# M117C.net
KiCad netlist of a schematic drawn in EAGLE
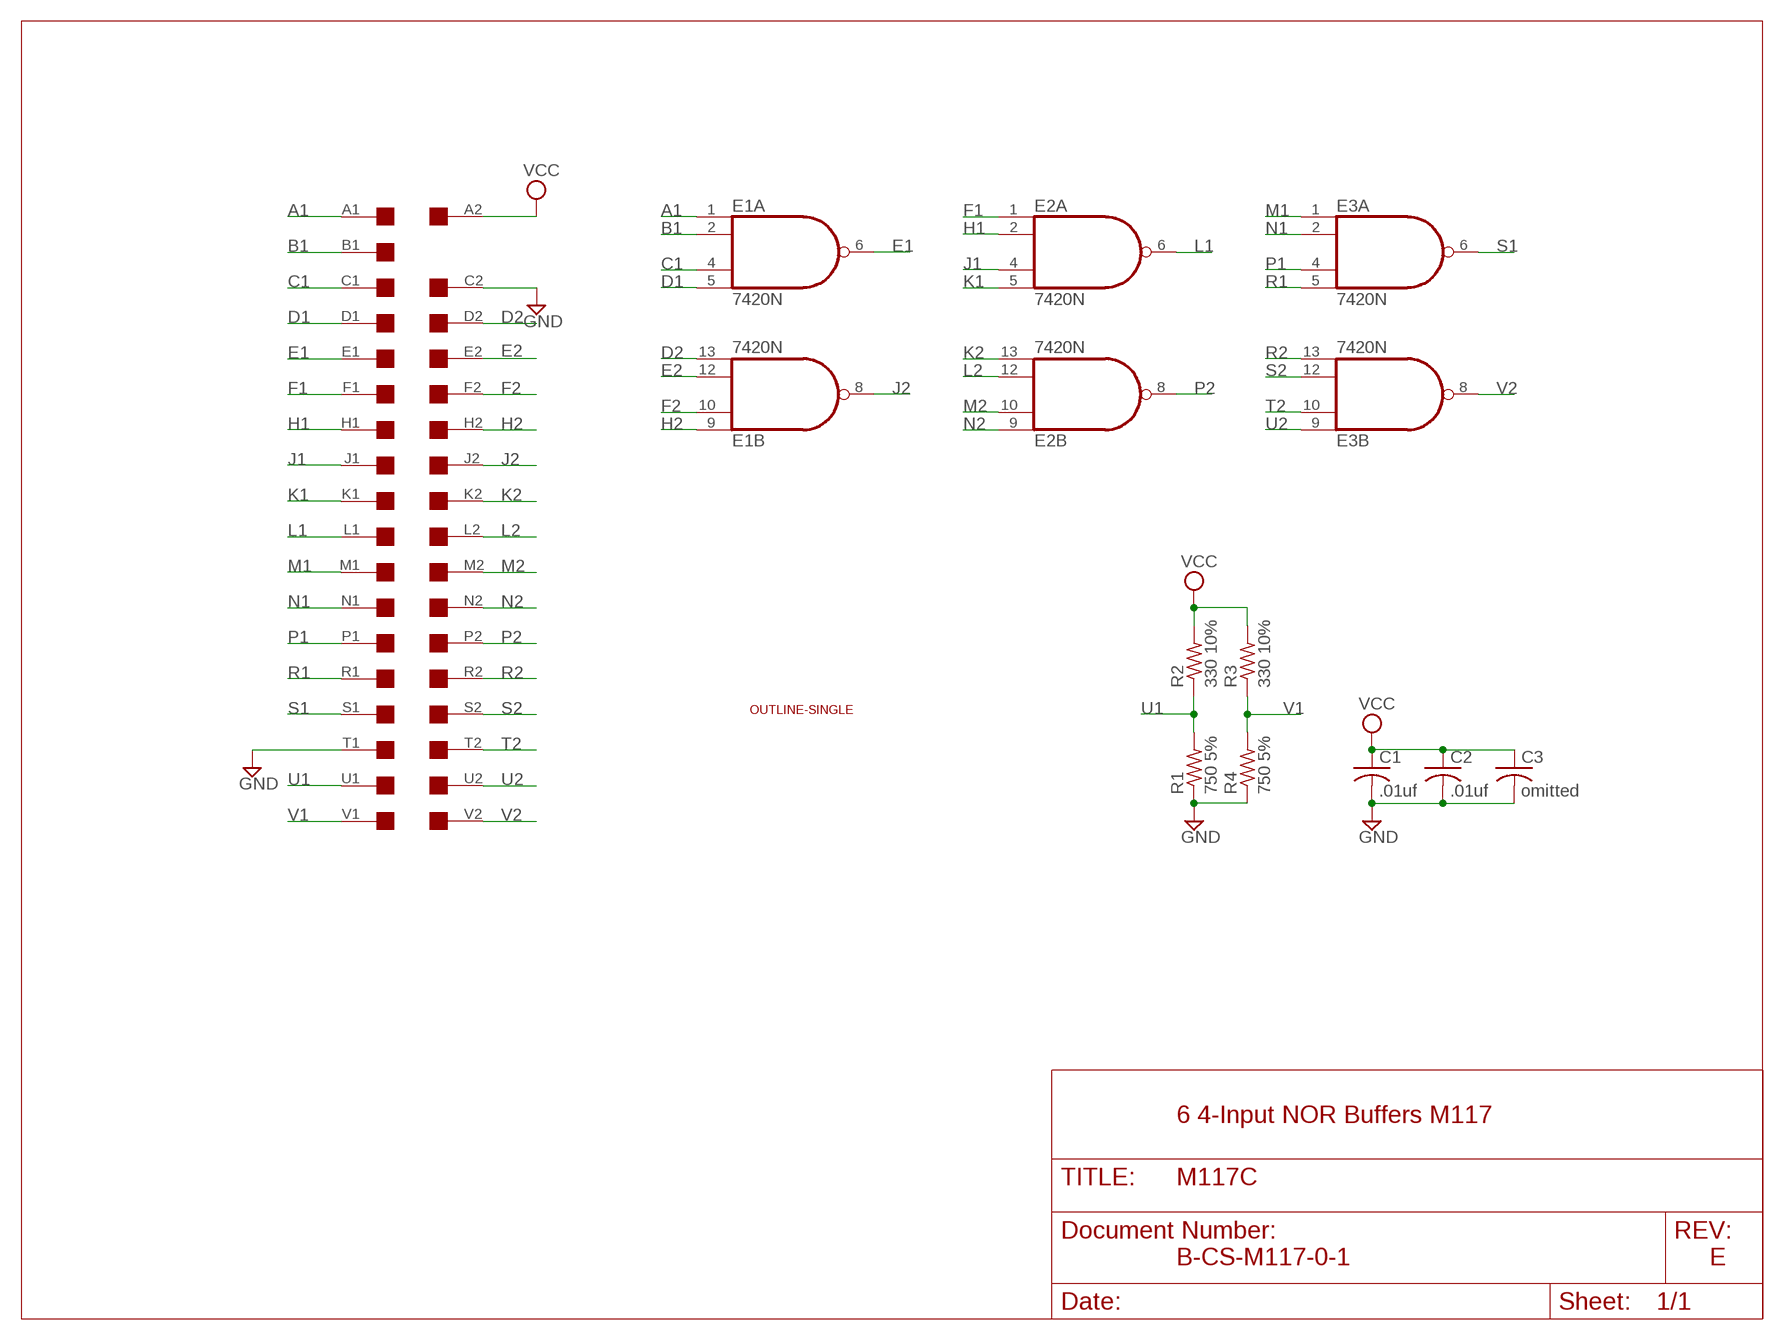
[diagram p0: schematic, sheet 1]

(export (version "E")
  (design (tool "Eeschema 10.0.6"))
  (components
    (comp (ref "C1")
      (value ".01uf")
      (footprint "eagle-import:C050-025X075")
      (libsource (lib "eagle-import") (part "C-US050-025X075"))
    )
    (comp (ref "C2")
      (value ".01uf")
      (footprint "eagle-import:C050-025X075")
      (libsource (lib "eagle-import") (part "C-US050-025X075"))
    )
    (comp (ref "C3")
      (value "omitted")
      (footprint "eagle-import:C050-025X075")
      (libsource (lib "eagle-import") (part "C-US050-025X075"))
    )
    (comp (ref "E1")
      (value "7420N")
      (footprint "eagle-import:DIL14")
      (libsource (lib "eagle-import") (part "7420NS"))
    )
    (comp (ref "E2")
      (value "7420N")
      (footprint "eagle-import:DIL14")
      (libsource (lib "eagle-import") (part "7420NS"))
    )
    (comp (ref "E3")
      (value "7420N")
      (footprint "eagle-import:DIL14")
      (libsource (lib "eagle-import") (part "7420NS"))
    )
    (comp (ref "R1")
      (value "750 5%")
      (footprint "eagle-import:0207_10")
      (libsource (lib "eagle-import") (part "R-US_0207/10"))
    )
    (comp (ref "R2")
      (value "330 10%")
      (footprint "eagle-import:0207_10")
      (libsource (lib "eagle-import") (part "R-US_0207/10"))
    )
    (comp (ref "R3")
      (value "330 10%")
      (footprint "eagle-import:0207_10")
      (libsource (lib "eagle-import") (part "R-US_0207/10"))
    )
    (comp (ref "R4")
      (value "750 5%")
      (footprint "eagle-import:0207_10")
      (libsource (lib "eagle-import") (part "R-US_0207/10"))
    )
    (comp (ref "U$1")
      (value "SINGLE")
      (footprint "eagle-import:EDGE-CON2")
      (libsource (lib "eagle-import") (part "SINGLE"))
    )
    (comp (ref "U$4")
      (value "OUTLINE-SINGLE")
      (footprint "eagle-import:SINGLE")
      (libsource (lib "eagle-import") (part "OUTLINE-SINGLE"))
    )
  )
  (nets
    (net (code "1") (name "/A1") (class "Default")
      (node (ref "E1") (pin "1") (pinfunction "I0_1") (pintype "input"))
      (node (ref "U$1") (pin "A1") (pinfunction "1_A1") (pintype "bidirectional"))
    )
    (net (code "2") (name "/B1") (class "Default")
      (node (ref "E1") (pin "2") (pinfunction "I1_2") (pintype "input"))
      (node (ref "U$1") (pin "B1") (pinfunction "1_B1") (pintype "bidirectional"))
    )
    (net (code "3") (name "/C1") (class "Default")
      (node (ref "E1") (pin "4") (pinfunction "I2_4") (pintype "input"))
      (node (ref "U$1") (pin "C1") (pinfunction "1_C1") (pintype "bidirectional"))
    )
    (net (code "4") (name "/D1") (class "Default")
      (node (ref "E1") (pin "5") (pinfunction "I3_5") (pintype "input"))
      (node (ref "U$1") (pin "D1") (pinfunction "1_D1") (pintype "bidirectional"))
    )
    (net (code "5") (name "/D2") (class "Default")
      (node (ref "E1") (pin "13") (pinfunction "I3_13") (pintype "input"))
      (node (ref "U$1") (pin "D2") (pinfunction "1_D2") (pintype "bidirectional"))
    )
    (net (code "6") (name "/E1") (class "Default")
      (node (ref "E1") (pin "6") (pinfunction "O_6") (pintype "output"))
      (node (ref "U$1") (pin "E1") (pinfunction "1_E1") (pintype "bidirectional"))
    )
    (net (code "7") (name "/E2") (class "Default")
      (node (ref "E1") (pin "12") (pinfunction "I2_12") (pintype "input"))
      (node (ref "U$1") (pin "E2") (pinfunction "1_E2") (pintype "bidirectional"))
    )
    (net (code "8") (name "/F1") (class "Default")
      (node (ref "E2") (pin "1") (pinfunction "I0_1") (pintype "input"))
      (node (ref "U$1") (pin "F1") (pinfunction "1_F1") (pintype "bidirectional"))
    )
    (net (code "9") (name "/F2") (class "Default")
      (node (ref "E1") (pin "10") (pinfunction "I1_10") (pintype "input"))
      (node (ref "U$1") (pin "F2") (pinfunction "1_F2") (pintype "bidirectional"))
    )
    (net (code "10") (name "/H1") (class "Default")
      (node (ref "E2") (pin "2") (pinfunction "I1_2") (pintype "input"))
      (node (ref "U$1") (pin "H1") (pinfunction "1_H1") (pintype "bidirectional"))
    )
    (net (code "11") (name "/H2") (class "Default")
      (node (ref "E1") (pin "9") (pinfunction "I0_9") (pintype "input"))
      (node (ref "U$1") (pin "H2") (pinfunction "1_H2") (pintype "bidirectional"))
    )
    (net (code "12") (name "/J1") (class "Default")
      (node (ref "E2") (pin "4") (pinfunction "I2_4") (pintype "input"))
      (node (ref "U$1") (pin "J1") (pinfunction "1_J1") (pintype "bidirectional"))
    )
    (net (code "13") (name "/J2") (class "Default")
      (node (ref "E1") (pin "8") (pinfunction "O_8") (pintype "output"))
      (node (ref "U$1") (pin "J2") (pinfunction "1_J2") (pintype "bidirectional"))
    )
    (net (code "14") (name "/K1") (class "Default")
      (node (ref "E2") (pin "5") (pinfunction "I3_5") (pintype "input"))
      (node (ref "U$1") (pin "K1") (pinfunction "1_K1") (pintype "bidirectional"))
    )
    (net (code "15") (name "/K2") (class "Default")
      (node (ref "E2") (pin "13") (pinfunction "I3_13") (pintype "input"))
      (node (ref "U$1") (pin "K2") (pinfunction "1_K2") (pintype "bidirectional"))
    )
    (net (code "16") (name "/L1") (class "Default")
      (node (ref "E2") (pin "6") (pinfunction "O_6") (pintype "output"))
      (node (ref "U$1") (pin "L1") (pinfunction "1_L1") (pintype "bidirectional"))
    )
    (net (code "17") (name "/L2") (class "Default")
      (node (ref "E2") (pin "12") (pinfunction "I2_12") (pintype "input"))
      (node (ref "U$1") (pin "L2") (pinfunction "1_L2") (pintype "bidirectional"))
    )
    (net (code "18") (name "/M1") (class "Default")
      (node (ref "E3") (pin "1") (pinfunction "I0_1") (pintype "input"))
      (node (ref "U$1") (pin "M1") (pinfunction "1_M1") (pintype "bidirectional"))
    )
    (net (code "19") (name "/M2") (class "Default")
      (node (ref "E2") (pin "10") (pinfunction "I1_10") (pintype "input"))
      (node (ref "U$1") (pin "M2") (pinfunction "1_M2") (pintype "bidirectional"))
    )
    (net (code "20") (name "/N1") (class "Default")
      (node (ref "E3") (pin "2") (pinfunction "I1_2") (pintype "input"))
      (node (ref "U$1") (pin "N1") (pinfunction "1_N1") (pintype "bidirectional"))
    )
    (net (code "21") (name "/N2") (class "Default")
      (node (ref "E2") (pin "9") (pinfunction "I0_9") (pintype "input"))
      (node (ref "U$1") (pin "N2") (pinfunction "1_N2") (pintype "bidirectional"))
    )
    (net (code "22") (name "/P1") (class "Default")
      (node (ref "E3") (pin "4") (pinfunction "I2_4") (pintype "input"))
      (node (ref "U$1") (pin "P1") (pinfunction "1_P1") (pintype "bidirectional"))
    )
    (net (code "23") (name "/P2") (class "Default")
      (node (ref "E2") (pin "8") (pinfunction "O_8") (pintype "output"))
      (node (ref "U$1") (pin "P2") (pinfunction "1_P2") (pintype "bidirectional"))
    )
    (net (code "24") (name "/R1") (class "Default")
      (node (ref "E3") (pin "5") (pinfunction "I3_5") (pintype "input"))
      (node (ref "U$1") (pin "R1") (pinfunction "1_R1") (pintype "bidirectional"))
    )
    (net (code "25") (name "/R2") (class "Default")
      (node (ref "E3") (pin "13") (pinfunction "I3_13") (pintype "input"))
      (node (ref "U$1") (pin "R2") (pinfunction "1_R2") (pintype "bidirectional"))
    )
    (net (code "26") (name "/S1") (class "Default")
      (node (ref "E3") (pin "6") (pinfunction "O_6") (pintype "output"))
      (node (ref "U$1") (pin "S1") (pinfunction "1_S1") (pintype "bidirectional"))
    )
    (net (code "27") (name "/S2") (class "Default")
      (node (ref "E3") (pin "12") (pinfunction "I2_12") (pintype "input"))
      (node (ref "U$1") (pin "S2") (pinfunction "1_S2") (pintype "bidirectional"))
    )
    (net (code "28") (name "/T2") (class "Default")
      (node (ref "E3") (pin "10") (pinfunction "I1_10") (pintype "input"))
      (node (ref "U$1") (pin "T2") (pinfunction "1_T2") (pintype "bidirectional"))
    )
    (net (code "29") (name "/U1") (class "Default")
      (node (ref "R1") (pin "2") (pinfunction "2_2") (pintype "passive"))
      (node (ref "R2") (pin "1") (pinfunction "1_1") (pintype "passive"))
      (node (ref "U$1") (pin "U1") (pinfunction "1_U1") (pintype "bidirectional"))
    )
    (net (code "30") (name "/U2") (class "Default")
      (node (ref "E3") (pin "9") (pinfunction "I0_9") (pintype "input"))
      (node (ref "U$1") (pin "U2") (pinfunction "1_U2") (pintype "bidirectional"))
    )
    (net (code "31") (name "/V1") (class "Default")
      (node (ref "R3") (pin "1") (pinfunction "1_1") (pintype "passive"))
      (node (ref "R4") (pin "2") (pinfunction "2_2") (pintype "passive"))
      (node (ref "U$1") (pin "V1") (pinfunction "1_V1") (pintype "bidirectional"))
    )
    (net (code "32") (name "/V2") (class "Default")
      (node (ref "E3") (pin "8") (pinfunction "O_8") (pintype "output"))
      (node (ref "U$1") (pin "V2") (pinfunction "1_V2") (pintype "bidirectional"))
    )
    (net (code "33") (name "GND") (class "Default")
      (node (ref "C1") (pin "2") (pinfunction "2_2") (pintype "passive"))
      (node (ref "C2") (pin "2") (pinfunction "2_2") (pintype "passive"))
      (node (ref "C3") (pin "2") (pinfunction "2_2") (pintype "passive"))
      (node (ref "R1") (pin "1") (pinfunction "1_1") (pintype "passive"))
      (node (ref "R4") (pin "1") (pinfunction "1_1") (pintype "passive"))
      (node (ref "U$1") (pin "C2") (pinfunction "1_C2") (pintype "bidirectional"))
      (node (ref "U$1") (pin "T1") (pinfunction "1_T1") (pintype "bidirectional"))
    )
    (net (code "34") (name "VCC") (class "Default")
      (node (ref "C1") (pin "1") (pinfunction "1_1") (pintype "passive"))
      (node (ref "C2") (pin "1") (pinfunction "1_1") (pintype "passive"))
      (node (ref "C3") (pin "1") (pinfunction "1_1") (pintype "passive"))
      (node (ref "R2") (pin "2") (pinfunction "2_2") (pintype "passive"))
      (node (ref "R3") (pin "2") (pinfunction "2_2") (pintype "passive"))
      (node (ref "U$1") (pin "A2") (pinfunction "1_A2") (pintype "bidirectional"))
    )
  )
)
